# McPiFace-RGBPanel-V2.net
KiCad netlist of a schematic drawn in EAGLE
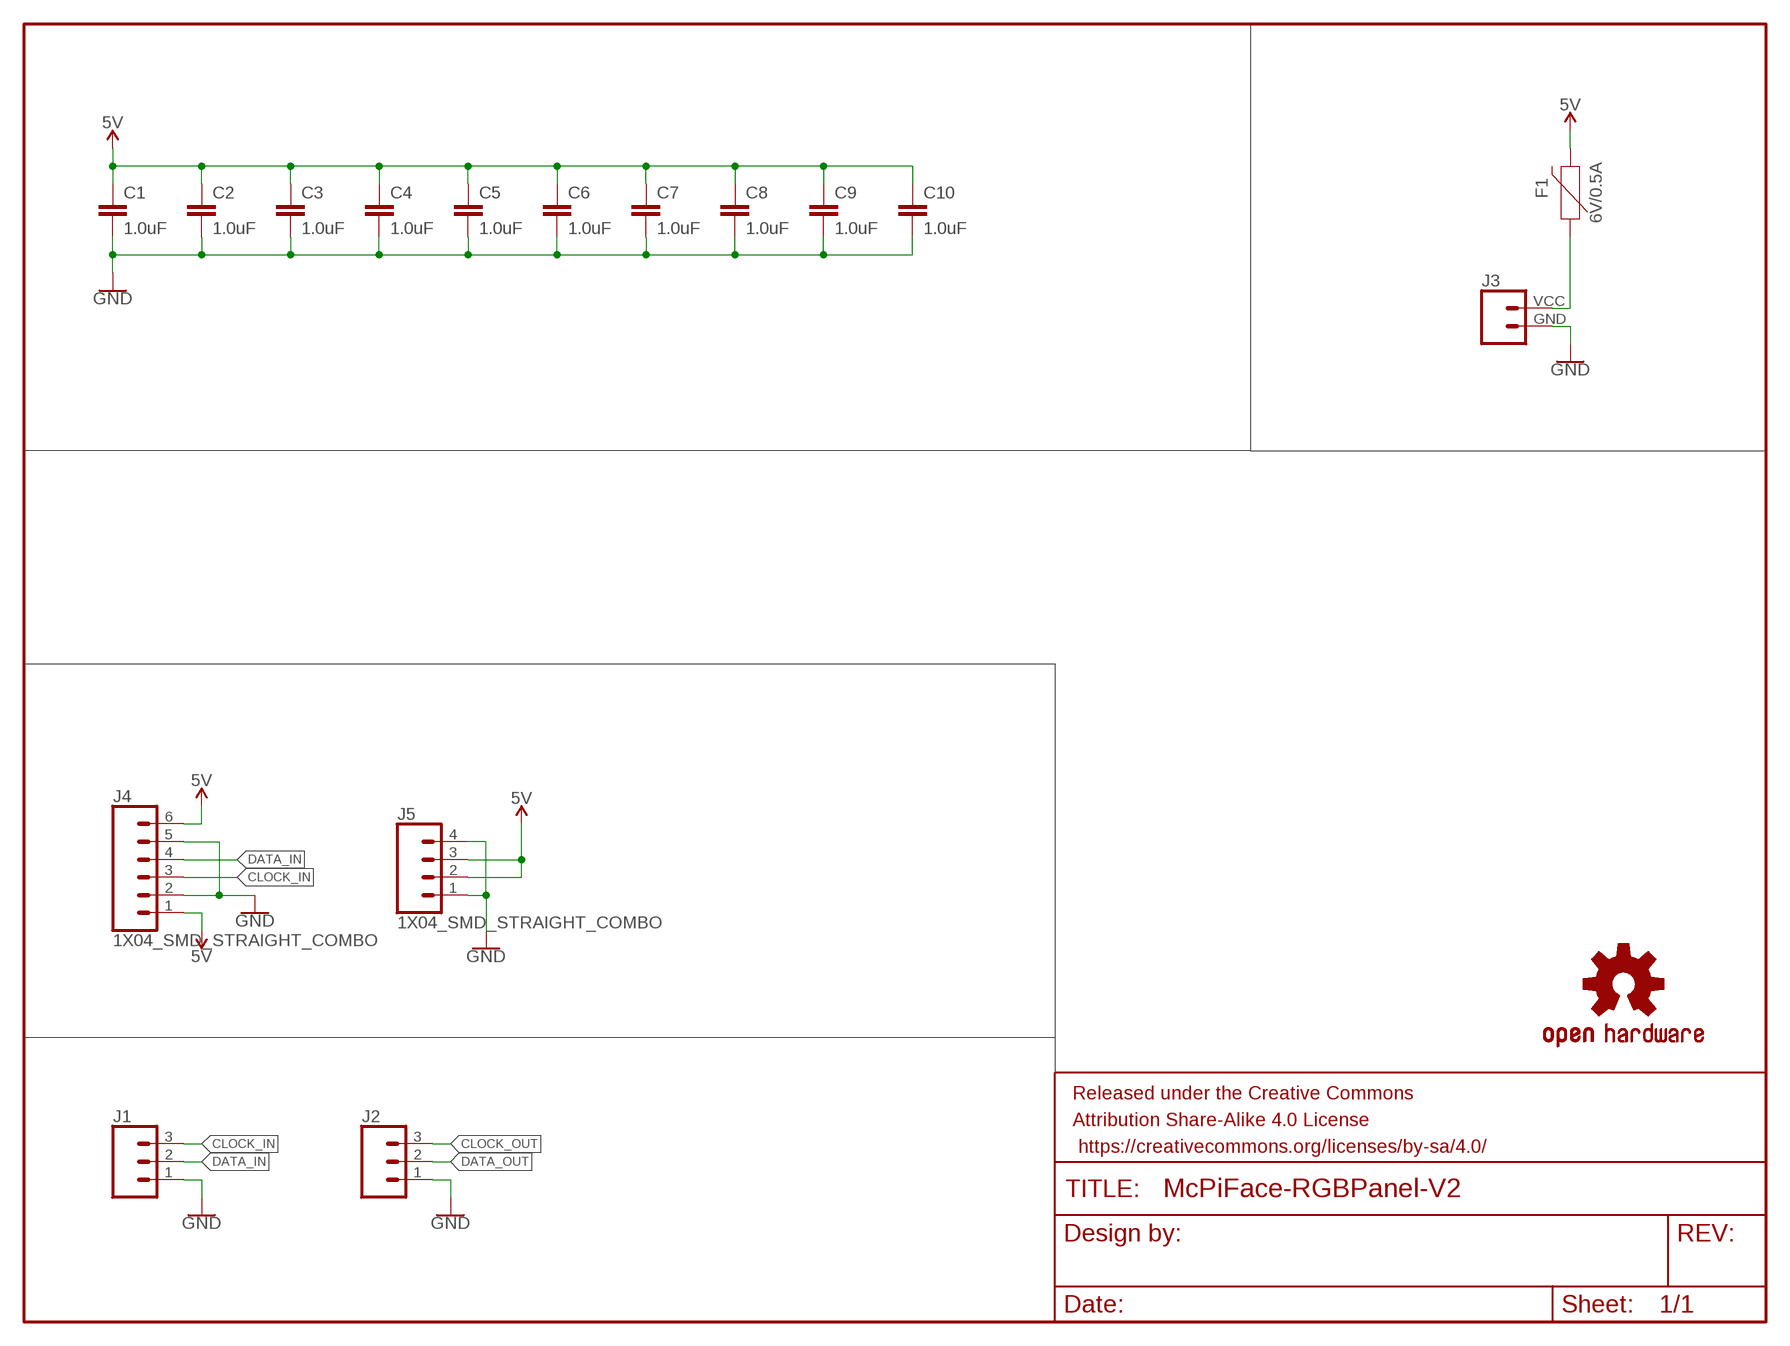
[diagram p0: schematic, sheet 1, part 1 of 2]
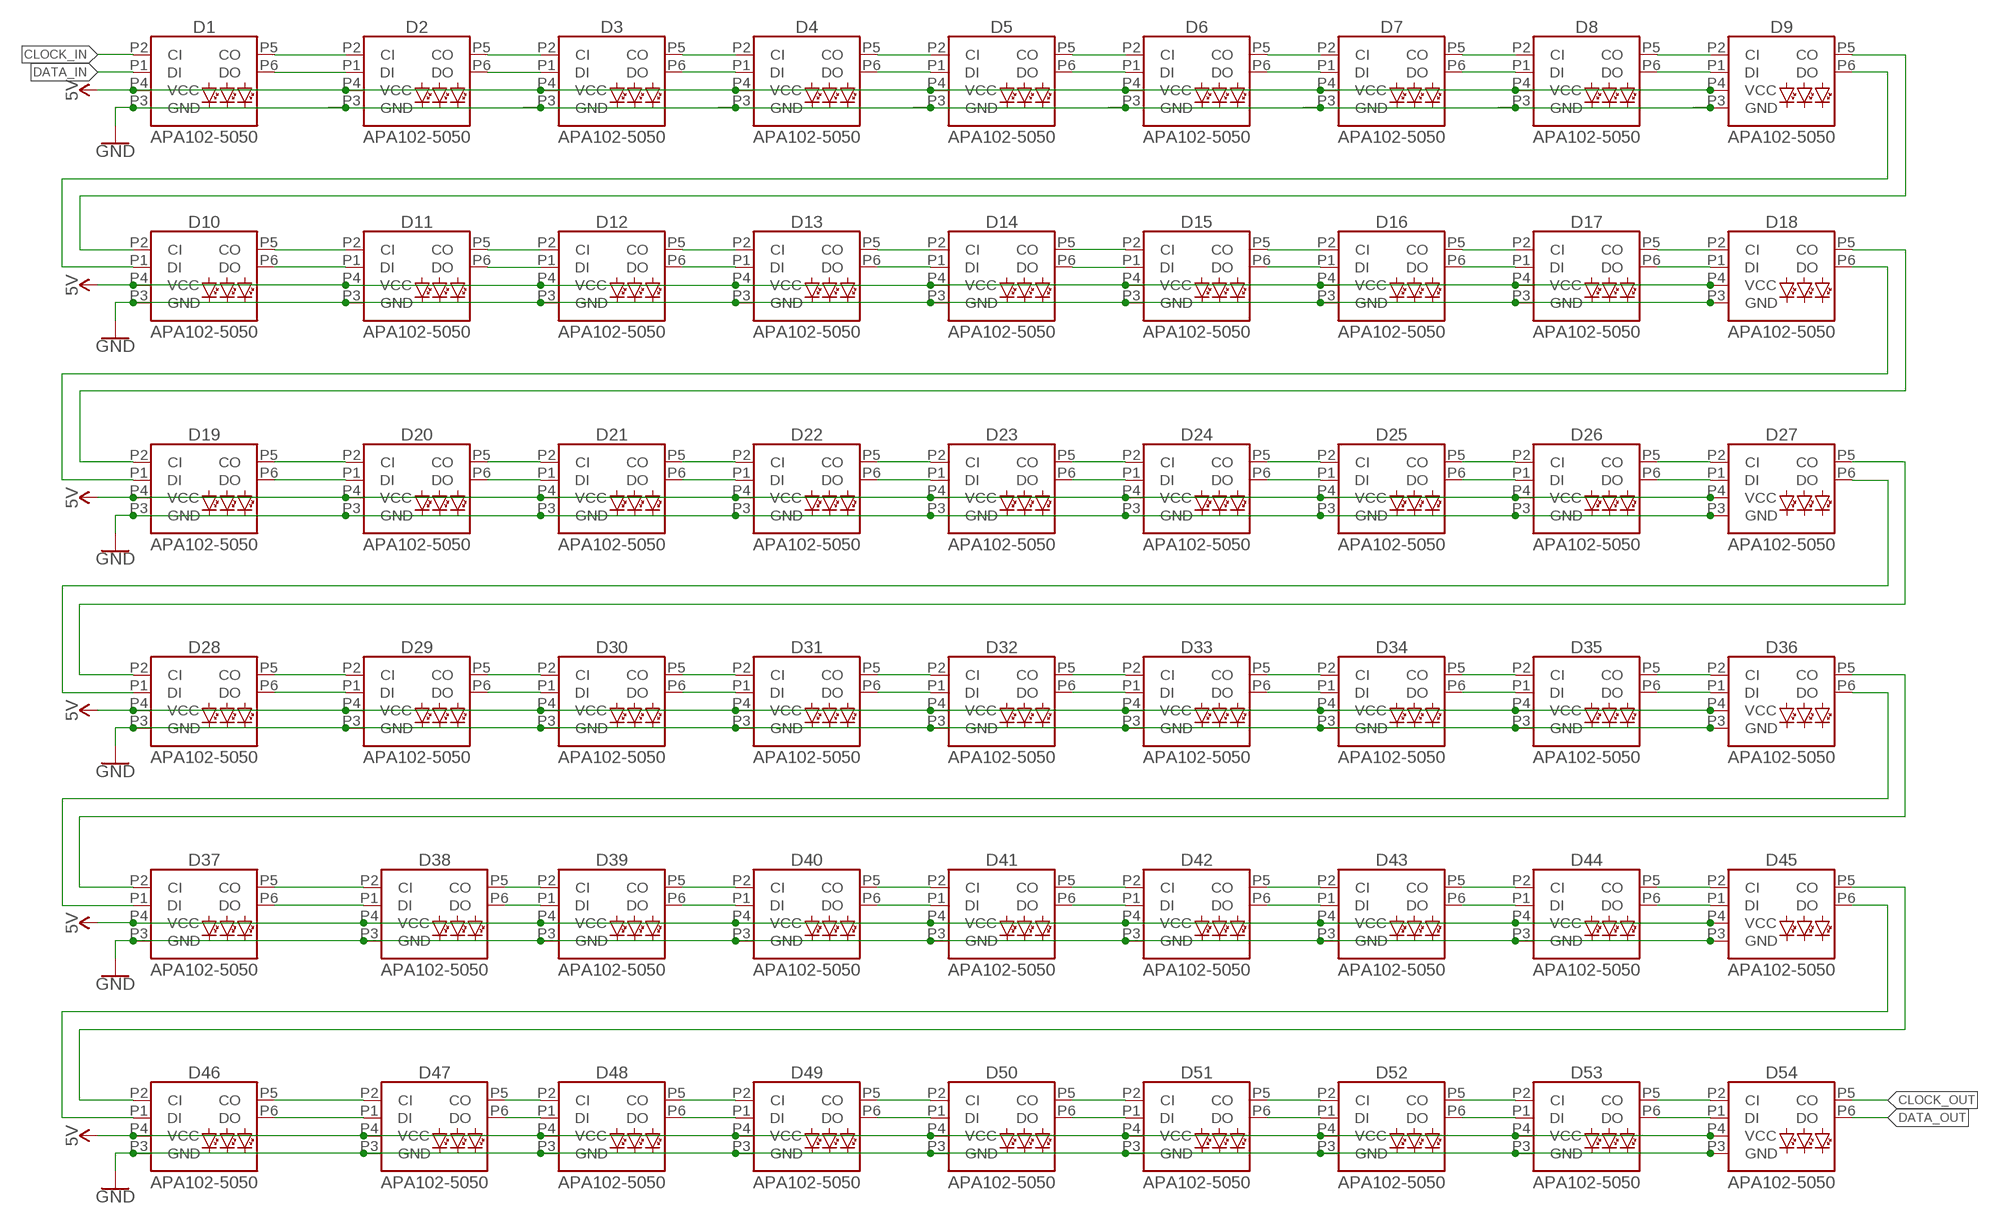
[diagram p1: schematic, sheet 1, part 2 of 2]

(export (version "E")
  (design (tool "Eeschema 10.0.6"))
  (components
    (comp (ref "C1")
      (value "1.0uF")
      (footprint "eagle-import:0805-CAP")
      (libsource (lib "eagle-import") (part "1.0UF-25V-+80/-20(0805){dblquote}"))
    )
    (comp (ref "C2")
      (value "1.0uF")
      (footprint "eagle-import:0805-CAP")
      (libsource (lib "eagle-import") (part "1.0UF-25V-+80/-20(0805){dblquote}"))
    )
    (comp (ref "C3")
      (value "1.0uF")
      (footprint "eagle-import:0805-CAP")
      (libsource (lib "eagle-import") (part "1.0UF-25V-+80/-20(0805){dblquote}"))
    )
    (comp (ref "C4")
      (value "1.0uF")
      (footprint "eagle-import:0805-CAP")
      (libsource (lib "eagle-import") (part "1.0UF-25V-+80/-20(0805){dblquote}"))
    )
    (comp (ref "C5")
      (value "1.0uF")
      (footprint "eagle-import:0805-CAP")
      (libsource (lib "eagle-import") (part "1.0UF-25V-+80/-20(0805){dblquote}"))
    )
    (comp (ref "C6")
      (value "1.0uF")
      (footprint "eagle-import:0805-CAP")
      (libsource (lib "eagle-import") (part "1.0UF-25V-+80/-20(0805){dblquote}"))
    )
    (comp (ref "C7")
      (value "1.0uF")
      (footprint "eagle-import:0805-CAP")
      (libsource (lib "eagle-import") (part "1.0UF-25V-+80/-20(0805){dblquote}"))
    )
    (comp (ref "C8")
      (value "1.0uF")
      (footprint "eagle-import:0805-CAP")
      (libsource (lib "eagle-import") (part "1.0UF-25V-+80/-20(0805){dblquote}"))
    )
    (comp (ref "C9")
      (value "1.0uF")
      (footprint "eagle-import:0805-CAP")
      (libsource (lib "eagle-import") (part "1.0UF-25V-+80/-20(0805){dblquote}"))
    )
    (comp (ref "C10")
      (value "1.0uF")
      (footprint "eagle-import:0805-CAP")
      (libsource (lib "eagle-import") (part "1.0UF-25V-+80/-20(0805){dblquote}"))
    )
    (comp (ref "D1")
      (value "APA102-5050")
      (footprint "eagle-import:APA102-5050")
      (libsource (lib "eagle-import") (part "APA102-5050"))
    )
    (comp (ref "D2")
      (value "APA102-5050")
      (footprint "eagle-import:APA102-5050")
      (libsource (lib "eagle-import") (part "APA102-5050"))
    )
    (comp (ref "D3")
      (value "APA102-5050")
      (footprint "eagle-import:APA102-5050")
      (libsource (lib "eagle-import") (part "APA102-5050"))
    )
    (comp (ref "D4")
      (value "APA102-5050")
      (footprint "eagle-import:APA102-5050")
      (libsource (lib "eagle-import") (part "APA102-5050"))
    )
    (comp (ref "D5")
      (value "APA102-5050")
      (footprint "eagle-import:APA102-5050")
      (libsource (lib "eagle-import") (part "APA102-5050"))
    )
    (comp (ref "D6")
      (value "APA102-5050")
      (footprint "eagle-import:APA102-5050")
      (libsource (lib "eagle-import") (part "APA102-5050"))
    )
    (comp (ref "D7")
      (value "APA102-5050")
      (footprint "eagle-import:APA102-5050")
      (libsource (lib "eagle-import") (part "APA102-5050"))
    )
    (comp (ref "D8")
      (value "APA102-5050")
      (footprint "eagle-import:APA102-5050")
      (libsource (lib "eagle-import") (part "APA102-5050"))
    )
    (comp (ref "D9")
      (value "APA102-5050")
      (footprint "eagle-import:APA102-5050")
      (libsource (lib "eagle-import") (part "APA102-5050"))
    )
    (comp (ref "D10")
      (value "APA102-5050")
      (footprint "eagle-import:APA102-5050")
      (libsource (lib "eagle-import") (part "APA102-5050"))
    )
    (comp (ref "D11")
      (value "APA102-5050")
      (footprint "eagle-import:APA102-5050")
      (libsource (lib "eagle-import") (part "APA102-5050"))
    )
    (comp (ref "D12")
      (value "APA102-5050")
      (footprint "eagle-import:APA102-5050")
      (libsource (lib "eagle-import") (part "APA102-5050"))
    )
    (comp (ref "D13")
      (value "APA102-5050")
      (footprint "eagle-import:APA102-5050")
      (libsource (lib "eagle-import") (part "APA102-5050"))
    )
    (comp (ref "D14")
      (value "APA102-5050")
      (footprint "eagle-import:APA102-5050")
      (libsource (lib "eagle-import") (part "APA102-5050"))
    )
    (comp (ref "D15")
      (value "APA102-5050")
      (footprint "eagle-import:APA102-5050")
      (libsource (lib "eagle-import") (part "APA102-5050"))
    )
    (comp (ref "D16")
      (value "APA102-5050")
      (footprint "eagle-import:APA102-5050")
      (libsource (lib "eagle-import") (part "APA102-5050"))
    )
    (comp (ref "D17")
      (value "APA102-5050")
      (footprint "eagle-import:APA102-5050")
      (libsource (lib "eagle-import") (part "APA102-5050"))
    )
    (comp (ref "D18")
      (value "APA102-5050")
      (footprint "eagle-import:APA102-5050")
      (libsource (lib "eagle-import") (part "APA102-5050"))
    )
    (comp (ref "D19")
      (value "APA102-5050")
      (footprint "eagle-import:APA102-5050")
      (libsource (lib "eagle-import") (part "APA102-5050"))
    )
    (comp (ref "D20")
      (value "APA102-5050")
      (footprint "eagle-import:APA102-5050")
      (libsource (lib "eagle-import") (part "APA102-5050"))
    )
    (comp (ref "D21")
      (value "APA102-5050")
      (footprint "eagle-import:APA102-5050")
      (libsource (lib "eagle-import") (part "APA102-5050"))
    )
    (comp (ref "D22")
      (value "APA102-5050")
      (footprint "eagle-import:APA102-5050")
      (libsource (lib "eagle-import") (part "APA102-5050"))
    )
    (comp (ref "D23")
      (value "APA102-5050")
      (footprint "eagle-import:APA102-5050")
      (libsource (lib "eagle-import") (part "APA102-5050"))
    )
    (comp (ref "D24")
      (value "APA102-5050")
      (footprint "eagle-import:APA102-5050")
      (libsource (lib "eagle-import") (part "APA102-5050"))
    )
    (comp (ref "D25")
      (value "APA102-5050")
      (footprint "eagle-import:APA102-5050")
      (libsource (lib "eagle-import") (part "APA102-5050"))
    )
    (comp (ref "D26")
      (value "APA102-5050")
      (footprint "eagle-import:APA102-5050")
      (libsource (lib "eagle-import") (part "APA102-5050"))
    )
    (comp (ref "D27")
      (value "APA102-5050")
      (footprint "eagle-import:APA102-5050")
      (libsource (lib "eagle-import") (part "APA102-5050"))
    )
    (comp (ref "D28")
      (value "APA102-5050")
      (footprint "eagle-import:APA102-5050")
      (libsource (lib "eagle-import") (part "APA102-5050"))
    )
    (comp (ref "D29")
      (value "APA102-5050")
      (footprint "eagle-import:APA102-5050")
      (libsource (lib "eagle-import") (part "APA102-5050"))
    )
    (comp (ref "D30")
      (value "APA102-5050")
      (footprint "eagle-import:APA102-5050")
      (libsource (lib "eagle-import") (part "APA102-5050"))
    )
    (comp (ref "D31")
      (value "APA102-5050")
      (footprint "eagle-import:APA102-5050")
      (libsource (lib "eagle-import") (part "APA102-5050"))
    )
    (comp (ref "D32")
      (value "APA102-5050")
      (footprint "eagle-import:APA102-5050")
      (libsource (lib "eagle-import") (part "APA102-5050"))
    )
    (comp (ref "D33")
      (value "APA102-5050")
      (footprint "eagle-import:APA102-5050")
      (libsource (lib "eagle-import") (part "APA102-5050"))
    )
    (comp (ref "D34")
      (value "APA102-5050")
      (footprint "eagle-import:APA102-5050")
      (libsource (lib "eagle-import") (part "APA102-5050"))
    )
    (comp (ref "D35")
      (value "APA102-5050")
      (footprint "eagle-import:APA102-5050")
      (libsource (lib "eagle-import") (part "APA102-5050"))
    )
    (comp (ref "D36")
      (value "APA102-5050")
      (footprint "eagle-import:APA102-5050")
      (libsource (lib "eagle-import") (part "APA102-5050"))
    )
    (comp (ref "D37")
      (value "APA102-5050")
      (footprint "eagle-import:APA102-5050")
      (libsource (lib "eagle-import") (part "APA102-5050"))
    )
    (comp (ref "D38")
      (value "APA102-5050")
      (footprint "eagle-import:APA102-5050")
      (libsource (lib "eagle-import") (part "APA102-5050"))
    )
    (comp (ref "D39")
      (value "APA102-5050")
      (footprint "eagle-import:APA102-5050")
      (libsource (lib "eagle-import") (part "APA102-5050"))
    )
    (comp (ref "D40")
      (value "APA102-5050")
      (footprint "eagle-import:APA102-5050")
      (libsource (lib "eagle-import") (part "APA102-5050"))
    )
    (comp (ref "D41")
      (value "APA102-5050")
      (footprint "eagle-import:APA102-5050")
      (libsource (lib "eagle-import") (part "APA102-5050"))
    )
    (comp (ref "D42")
      (value "APA102-5050")
      (footprint "eagle-import:APA102-5050")
      (libsource (lib "eagle-import") (part "APA102-5050"))
    )
    (comp (ref "D43")
      (value "APA102-5050")
      (footprint "eagle-import:APA102-5050")
      (libsource (lib "eagle-import") (part "APA102-5050"))
    )
    (comp (ref "D44")
      (value "APA102-5050")
      (footprint "eagle-import:APA102-5050")
      (libsource (lib "eagle-import") (part "APA102-5050"))
    )
    (comp (ref "D45")
      (value "APA102-5050")
      (footprint "eagle-import:APA102-5050")
      (libsource (lib "eagle-import") (part "APA102-5050"))
    )
    (comp (ref "D46")
      (value "APA102-5050")
      (footprint "eagle-import:APA102-5050")
      (libsource (lib "eagle-import") (part "APA102-5050"))
    )
    (comp (ref "D47")
      (value "APA102-5050")
      (footprint "eagle-import:APA102-5050")
      (libsource (lib "eagle-import") (part "APA102-5050"))
    )
    (comp (ref "D48")
      (value "APA102-5050")
      (footprint "eagle-import:APA102-5050")
      (libsource (lib "eagle-import") (part "APA102-5050"))
    )
    (comp (ref "D49")
      (value "APA102-5050")
      (footprint "eagle-import:APA102-5050")
      (libsource (lib "eagle-import") (part "APA102-5050"))
    )
    (comp (ref "D50")
      (value "APA102-5050")
      (footprint "eagle-import:APA102-5050")
      (libsource (lib "eagle-import") (part "APA102-5050"))
    )
    (comp (ref "D51")
      (value "APA102-5050")
      (footprint "eagle-import:APA102-5050")
      (libsource (lib "eagle-import") (part "APA102-5050"))
    )
    (comp (ref "D52")
      (value "APA102-5050")
      (footprint "eagle-import:APA102-5050")
      (libsource (lib "eagle-import") (part "APA102-5050"))
    )
    (comp (ref "D53")
      (value "APA102-5050")
      (footprint "eagle-import:APA102-5050")
      (libsource (lib "eagle-import") (part "APA102-5050"))
    )
    (comp (ref "D54")
      (value "APA102-5050")
      (footprint "eagle-import:APA102-5050")
      (libsource (lib "eagle-import") (part "APA102-5050"))
    )
    (comp (ref "F1")
      (value "6V/0.5A")
      (footprint "eagle-import:1206")
      (libsource (lib "eagle-import") (part "PPTC_HALF-AMP"))
    )
    (comp (ref "FRAME1")
      (value "FRAME-LETTER")
      (footprint "eagle-import:CREATIVE_COMMONS")
      (libsource (lib "eagle-import") (part "FRAME-LETTER"))
    )
    (comp (ref "J1")
      (value "CONN_03SMD")
      (footprint "eagle-import:1X03-1MM-RA")
      (libsource (lib "eagle-import") (part "CONN_03SMD"))
    )
    (comp (ref "J2")
      (value "CONN_03SMD")
      (footprint "eagle-import:1X03-1MM-RA")
      (libsource (lib "eagle-import") (part "CONN_03SMD"))
    )
    (comp (ref "J3")
      (value "CONN_02JST-2-PH-VERT")
      (footprint "eagle-import:JST-2-SMD-VERT")
      (libsource (lib "eagle-import") (part "CONN_02JST-2-PH-VERT"))
    )
    (comp (ref "J4")
      (value "1X04_SMD_STRAIGHT_COMBO")
      (footprint "eagle-import:1X06_SMD_STRAIGHT_COMBO")
      (libsource (lib "eagle-import") (part "CONN_06SMD-STRAIGHT-COMBO-FEMALE"))
    )
    (comp (ref "J5")
      (value "1X04_SMD_STRAIGHT_COMBO")
      (footprint "eagle-import:1X04_SMD_VERTICAL_COMBO")
      (libsource (lib "eagle-import") (part "CONN_04SMD_STRAIGHT_COMBO"))
    )
    (comp (ref "LOGO1")
      (value "OSHW-LOGOL")
      (footprint "eagle-import:OSHW-LOGO-L")
      (libsource (lib "eagle-import") (part "OSHW-LOGOL"))
    )
  )
  (nets
    (net (code "1") (name "5V") (class "Default")
      (node (ref "C1") (pin "1") (pinfunction "1_1") (pintype "passive"))
      (node (ref "C10") (pin "1") (pinfunction "1_1") (pintype "passive"))
      (node (ref "C2") (pin "1") (pinfunction "1_1") (pintype "passive"))
      (node (ref "C3") (pin "1") (pinfunction "1_1") (pintype "passive"))
      (node (ref "C4") (pin "1") (pinfunction "1_1") (pintype "passive"))
      (node (ref "C5") (pin "1") (pinfunction "1_1") (pintype "passive"))
      (node (ref "C6") (pin "1") (pinfunction "1_1") (pintype "passive"))
      (node (ref "C7") (pin "1") (pinfunction "1_1") (pintype "passive"))
      (node (ref "C8") (pin "1") (pinfunction "1_1") (pintype "passive"))
      (node (ref "C9") (pin "1") (pinfunction "1_1") (pintype "passive"))
      (node (ref "D1") (pin "P4") (pinfunction "VCC_P4") (pintype "bidirectional"))
      (node (ref "D10") (pin "P4") (pinfunction "VCC_P4") (pintype "bidirectional"))
      (node (ref "D11") (pin "P4") (pinfunction "VCC_P4") (pintype "bidirectional"))
      (node (ref "D12") (pin "P4") (pinfunction "VCC_P4") (pintype "bidirectional"))
      (node (ref "D13") (pin "P4") (pinfunction "VCC_P4") (pintype "bidirectional"))
      (node (ref "D14") (pin "P4") (pinfunction "VCC_P4") (pintype "bidirectional"))
      (node (ref "D15") (pin "P4") (pinfunction "VCC_P4") (pintype "bidirectional"))
      (node (ref "D16") (pin "P4") (pinfunction "VCC_P4") (pintype "bidirectional"))
      (node (ref "D17") (pin "P4") (pinfunction "VCC_P4") (pintype "bidirectional"))
      (node (ref "D18") (pin "P4") (pinfunction "VCC_P4") (pintype "bidirectional"))
      (node (ref "D19") (pin "P4") (pinfunction "VCC_P4") (pintype "bidirectional"))
      (node (ref "D2") (pin "P4") (pinfunction "VCC_P4") (pintype "bidirectional"))
      (node (ref "D20") (pin "P4") (pinfunction "VCC_P4") (pintype "bidirectional"))
      (node (ref "D21") (pin "P4") (pinfunction "VCC_P4") (pintype "bidirectional"))
      (node (ref "D22") (pin "P4") (pinfunction "VCC_P4") (pintype "bidirectional"))
      (node (ref "D23") (pin "P4") (pinfunction "VCC_P4") (pintype "bidirectional"))
      (node (ref "D24") (pin "P4") (pinfunction "VCC_P4") (pintype "bidirectional"))
      (node (ref "D25") (pin "P4") (pinfunction "VCC_P4") (pintype "bidirectional"))
      (node (ref "D26") (pin "P4") (pinfunction "VCC_P4") (pintype "bidirectional"))
      (node (ref "D27") (pin "P4") (pinfunction "VCC_P4") (pintype "bidirectional"))
      (node (ref "D28") (pin "P4") (pinfunction "VCC_P4") (pintype "bidirectional"))
      (node (ref "D29") (pin "P4") (pinfunction "VCC_P4") (pintype "bidirectional"))
      (node (ref "D3") (pin "P4") (pinfunction "VCC_P4") (pintype "bidirectional"))
      (node (ref "D30") (pin "P4") (pinfunction "VCC_P4") (pintype "bidirectional"))
      (node (ref "D31") (pin "P4") (pinfunction "VCC_P4") (pintype "bidirectional"))
      (node (ref "D32") (pin "P4") (pinfunction "VCC_P4") (pintype "bidirectional"))
      (node (ref "D33") (pin "P4") (pinfunction "VCC_P4") (pintype "bidirectional"))
      (node (ref "D34") (pin "P4") (pinfunction "VCC_P4") (pintype "bidirectional"))
      (node (ref "D35") (pin "P4") (pinfunction "VCC_P4") (pintype "bidirectional"))
      (node (ref "D36") (pin "P4") (pinfunction "VCC_P4") (pintype "bidirectional"))
      (node (ref "D37") (pin "P4") (pinfunction "VCC_P4") (pintype "bidirectional"))
      (node (ref "D38") (pin "P4") (pinfunction "VCC_P4") (pintype "bidirectional"))
      (node (ref "D39") (pin "P4") (pinfunction "VCC_P4") (pintype "bidirectional"))
      (node (ref "D4") (pin "P4") (pinfunction "VCC_P4") (pintype "bidirectional"))
      (node (ref "D40") (pin "P4") (pinfunction "VCC_P4") (pintype "bidirectional"))
      (node (ref "D41") (pin "P4") (pinfunction "VCC_P4") (pintype "bidirectional"))
      (node (ref "D42") (pin "P4") (pinfunction "VCC_P4") (pintype "bidirectional"))
      (node (ref "D43") (pin "P4") (pinfunction "VCC_P4") (pintype "bidirectional"))
      (node (ref "D44") (pin "P4") (pinfunction "VCC_P4") (pintype "bidirectional"))
      (node (ref "D45") (pin "P4") (pinfunction "VCC_P4") (pintype "bidirectional"))
      (node (ref "D46") (pin "P4") (pinfunction "VCC_P4") (pintype "bidirectional"))
      (node (ref "D47") (pin "P4") (pinfunction "VCC_P4") (pintype "bidirectional"))
      (node (ref "D48") (pin "P4") (pinfunction "VCC_P4") (pintype "bidirectional"))
      (node (ref "D49") (pin "P4") (pinfunction "VCC_P4") (pintype "bidirectional"))
      (node (ref "D5") (pin "P4") (pinfunction "VCC_P4") (pintype "bidirectional"))
      (node (ref "D50") (pin "P4") (pinfunction "VCC_P4") (pintype "bidirectional"))
      (node (ref "D51") (pin "P4") (pinfunction "VCC_P4") (pintype "bidirectional"))
      (node (ref "D52") (pin "P4") (pinfunction "VCC_P4") (pintype "bidirectional"))
      (node (ref "D53") (pin "P4") (pinfunction "VCC_P4") (pintype "bidirectional"))
      (node (ref "D54") (pin "P4") (pinfunction "VCC_P4") (pintype "bidirectional"))
      (node (ref "D6") (pin "P4") (pinfunction "VCC_P4") (pintype "bidirectional"))
      (node (ref "D7") (pin "P4") (pinfunction "VCC_P4") (pintype "bidirectional"))
      (node (ref "D8") (pin "P4") (pinfunction "VCC_P4") (pintype "bidirectional"))
      (node (ref "D9") (pin "P4") (pinfunction "VCC_P4") (pintype "bidirectional"))
      (node (ref "F1") (pin "2") (pinfunction "2_2") (pintype "bidirectional"))
      (node (ref "J4") (pin "1") (pinfunction "1_1") (pintype "passive"))
      (node (ref "J4") (pin "6") (pinfunction "6_6") (pintype "passive"))
      (node (ref "J5") (pin "2") (pinfunction "2_2") (pintype "passive"))
      (node (ref "J5") (pin "3") (pinfunction "3_3") (pintype "passive"))
    )
    (net (code "2") (name "CLOCK_IN") (class "Default")
      (node (ref "D1") (pin "P2") (pinfunction "CI_P2") (pintype "bidirectional"))
      (node (ref "J1") (pin "3") (pinfunction "3_3") (pintype "passive"))
      (node (ref "J4") (pin "3") (pinfunction "3_3") (pintype "passive"))
    )
    (net (code "3") (name "CLOCK_OUT") (class "Default")
      (node (ref "D54") (pin "P5") (pinfunction "CO_P5") (pintype "bidirectional"))
      (node (ref "J2") (pin "3") (pinfunction "3_3") (pintype "passive"))
    )
    (net (code "4") (name "DATA_IN") (class "Default")
      (node (ref "D1") (pin "P1") (pinfunction "DI_P1") (pintype "bidirectional"))
      (node (ref "J1") (pin "2") (pinfunction "2_2") (pintype "passive"))
      (node (ref "J4") (pin "4") (pinfunction "4_4") (pintype "passive"))
    )
    (net (code "5") (name "DATA_OUT") (class "Default")
      (node (ref "D54") (pin "P6") (pinfunction "DO_P6") (pintype "bidirectional"))
      (node (ref "J2") (pin "2") (pinfunction "2_2") (pintype "passive"))
    )
    (net (code "6") (name "GND") (class "Default")
      (node (ref "C1") (pin "2") (pinfunction "2_2") (pintype "passive"))
      (node (ref "C10") (pin "2") (pinfunction "2_2") (pintype "passive"))
      (node (ref "C2") (pin "2") (pinfunction "2_2") (pintype "passive"))
      (node (ref "C3") (pin "2") (pinfunction "2_2") (pintype "passive"))
      (node (ref "C4") (pin "2") (pinfunction "2_2") (pintype "passive"))
      (node (ref "C5") (pin "2") (pinfunction "2_2") (pintype "passive"))
      (node (ref "C6") (pin "2") (pinfunction "2_2") (pintype "passive"))
      (node (ref "C7") (pin "2") (pinfunction "2_2") (pintype "passive"))
      (node (ref "C8") (pin "2") (pinfunction "2_2") (pintype "passive"))
      (node (ref "C9") (pin "2") (pinfunction "2_2") (pintype "passive"))
      (node (ref "D1") (pin "P3") (pinfunction "GND_P3") (pintype "bidirectional"))
      (node (ref "D10") (pin "P3") (pinfunction "GND_P3") (pintype "bidirectional"))
      (node (ref "D11") (pin "P3") (pinfunction "GND_P3") (pintype "bidirectional"))
      (node (ref "D12") (pin "P3") (pinfunction "GND_P3") (pintype "bidirectional"))
      (node (ref "D13") (pin "P3") (pinfunction "GND_P3") (pintype "bidirectional"))
      (node (ref "D14") (pin "P3") (pinfunction "GND_P3") (pintype "bidirectional"))
      (node (ref "D15") (pin "P3") (pinfunction "GND_P3") (pintype "bidirectional"))
      (node (ref "D16") (pin "P3") (pinfunction "GND_P3") (pintype "bidirectional"))
      (node (ref "D17") (pin "P3") (pinfunction "GND_P3") (pintype "bidirectional"))
      (node (ref "D18") (pin "P3") (pinfunction "GND_P3") (pintype "bidirectional"))
      (node (ref "D19") (pin "P3") (pinfunction "GND_P3") (pintype "bidirectional"))
      (node (ref "D2") (pin "P3") (pinfunction "GND_P3") (pintype "bidirectional"))
      (node (ref "D20") (pin "P3") (pinfunction "GND_P3") (pintype "bidirectional"))
      (node (ref "D21") (pin "P3") (pinfunction "GND_P3") (pintype "bidirectional"))
      (node (ref "D22") (pin "P3") (pinfunction "GND_P3") (pintype "bidirectional"))
      (node (ref "D23") (pin "P3") (pinfunction "GND_P3") (pintype "bidirectional"))
      (node (ref "D24") (pin "P3") (pinfunction "GND_P3") (pintype "bidirectional"))
      (node (ref "D25") (pin "P3") (pinfunction "GND_P3") (pintype "bidirectional"))
      (node (ref "D26") (pin "P3") (pinfunction "GND_P3") (pintype "bidirectional"))
      (node (ref "D27") (pin "P3") (pinfunction "GND_P3") (pintype "bidirectional"))
      (node (ref "D28") (pin "P3") (pinfunction "GND_P3") (pintype "bidirectional"))
      (node (ref "D29") (pin "P3") (pinfunction "GND_P3") (pintype "bidirectional"))
      (node (ref "D3") (pin "P3") (pinfunction "GND_P3") (pintype "bidirectional"))
      (node (ref "D30") (pin "P3") (pinfunction "GND_P3") (pintype "bidirectional"))
      (node (ref "D31") (pin "P3") (pinfunction "GND_P3") (pintype "bidirectional"))
      (node (ref "D32") (pin "P3") (pinfunction "GND_P3") (pintype "bidirectional"))
      (node (ref "D33") (pin "P3") (pinfunction "GND_P3") (pintype "bidirectional"))
      (node (ref "D34") (pin "P3") (pinfunction "GND_P3") (pintype "bidirectional"))
      (node (ref "D35") (pin "P3") (pinfunction "GND_P3") (pintype "bidirectional"))
      (node (ref "D36") (pin "P3") (pinfunction "GND_P3") (pintype "bidirectional"))
      (node (ref "D37") (pin "P3") (pinfunction "GND_P3") (pintype "bidirectional"))
      (node (ref "D38") (pin "P3") (pinfunction "GND_P3") (pintype "bidirectional"))
      (node (ref "D39") (pin "P3") (pinfunction "GND_P3") (pintype "bidirectional"))
      (node (ref "D4") (pin "P3") (pinfunction "GND_P3") (pintype "bidirectional"))
      (node (ref "D40") (pin "P3") (pinfunction "GND_P3") (pintype "bidirectional"))
      (node (ref "D41") (pin "P3") (pinfunction "GND_P3") (pintype "bidirectional"))
      (node (ref "D42") (pin "P3") (pinfunction "GND_P3") (pintype "bidirectional"))
      (node (ref "D43") (pin "P3") (pinfunction "GND_P3") (pintype "bidirectional"))
      (node (ref "D44") (pin "P3") (pinfunction "GND_P3") (pintype "bidirectional"))
      (node (ref "D45") (pin "P3") (pinfunction "GND_P3") (pintype "bidirectional"))
      (node (ref "D46") (pin "P3") (pinfunction "GND_P3") (pintype "bidirectional"))
      (node (ref "D47") (pin "P3") (pinfunction "GND_P3") (pintype "bidirectional"))
      (node (ref "D48") (pin "P3") (pinfunction "GND_P3") (pintype "bidirectional"))
      (node (ref "D49") (pin "P3") (pinfunction "GND_P3") (pintype "bidirectional"))
      (node (ref "D5") (pin "P3") (pinfunction "GND_P3") (pintype "bidirectional"))
      (node (ref "D50") (pin "P3") (pinfunction "GND_P3") (pintype "bidirectional"))
      (node (ref "D51") (pin "P3") (pinfunction "GND_P3") (pintype "bidirectional"))
      (node (ref "D52") (pin "P3") (pinfunction "GND_P3") (pintype "bidirectional"))
      (node (ref "D53") (pin "P3") (pinfunction "GND_P3") (pintype "bidirectional"))
      (node (ref "D54") (pin "P3") (pinfunction "GND_P3") (pintype "bidirectional"))
      (node (ref "D6") (pin "P3") (pinfunction "GND_P3") (pintype "bidirectional"))
      (node (ref "D7") (pin "P3") (pinfunction "GND_P3") (pintype "bidirectional"))
      (node (ref "D8") (pin "P3") (pinfunction "GND_P3") (pintype "bidirectional"))
      (node (ref "D9") (pin "P3") (pinfunction "GND_P3") (pintype "bidirectional"))
      (node (ref "J1") (pin "1") (pinfunction "1_1") (pintype "passive"))
      (node (ref "J2") (pin "1") (pinfunction "1_1") (pintype "passive"))
      (node (ref "J3") (pin "GND") (pinfunction "1_GND") (pintype "passive"))
      (node (ref "J4") (pin "2") (pinfunction "2_2") (pintype "passive"))
      (node (ref "J4") (pin "5") (pinfunction "5_5") (pintype "passive"))
      (node (ref "J5") (pin "1") (pinfunction "1_1") (pintype "passive"))
      (node (ref "J5") (pin "4") (pinfunction "4_4") (pintype "passive"))
    )
    (net (code "7") (name "Net-(D1-CO)") (class "Default")
      (node (ref "D1") (pin "P5") (pinfunction "CO_P5") (pintype "bidirectional"))
      (node (ref "D2") (pin "P2") (pinfunction "CI_P2") (pintype "bidirectional"))
    )
    (net (code "8") (name "Net-(D1-DO)") (class "Default")
      (node (ref "D1") (pin "P6") (pinfunction "DO_P6") (pintype "bidirectional"))
      (node (ref "D2") (pin "P1") (pinfunction "DI_P1") (pintype "bidirectional"))
    )
    (net (code "9") (name "Net-(D2-CO)") (class "Default")
      (node (ref "D2") (pin "P5") (pinfunction "CO_P5") (pintype "bidirectional"))
      (node (ref "D3") (pin "P2") (pinfunction "CI_P2") (pintype "bidirectional"))
    )
    (net (code "10") (name "Net-(D2-DO)") (class "Default")
      (node (ref "D2") (pin "P6") (pinfunction "DO_P6") (pintype "bidirectional"))
      (node (ref "D3") (pin "P1") (pinfunction "DI_P1") (pintype "bidirectional"))
    )
    (net (code "11") (name "Net-(D3-CO)") (class "Default")
      (node (ref "D3") (pin "P5") (pinfunction "CO_P5") (pintype "bidirectional"))
      (node (ref "D4") (pin "P2") (pinfunction "CI_P2") (pintype "bidirectional"))
    )
    (net (code "12") (name "Net-(D3-DO)") (class "Default")
      (node (ref "D3") (pin "P6") (pinfunction "DO_P6") (pintype "bidirectional"))
      (node (ref "D4") (pin "P1") (pinfunction "DI_P1") (pintype "bidirectional"))
    )
    (net (code "13") (name "Net-(D4-CO)") (class "Default")
      (node (ref "D4") (pin "P5") (pinfunction "CO_P5") (pintype "bidirectional"))
      (node (ref "D5") (pin "P2") (pinfunction "CI_P2") (pintype "bidirectional"))
    )
    (net (code "14") (name "Net-(D4-DO)") (class "Default")
      (node (ref "D4") (pin "P6") (pinfunction "DO_P6") (pintype "bidirectional"))
      (node (ref "D5") (pin "P1") (pinfunction "DI_P1") (pintype "bidirectional"))
    )
    (net (code "15") (name "Net-(D5-CO)") (class "Default")
      (node (ref "D5") (pin "P5") (pinfunction "CO_P5") (pintype "bidirectional"))
      (node (ref "D6") (pin "P2") (pinfunction "CI_P2") (pintype "bidirectional"))
    )
    (net (code "16") (name "Net-(D5-DO)") (class "Default")
      (node (ref "D5") (pin "P6") (pinfunction "DO_P6") (pintype "bidirectional"))
      (node (ref "D6") (pin "P1") (pinfunction "DI_P1") (pintype "bidirectional"))
    )
    (net (code "17") (name "Net-(D6-CO)") (class "Default")
      (node (ref "D6") (pin "P5") (pinfunction "CO_P5") (pintype "bidirectional"))
      (node (ref "D7") (pin "P2") (pinfunction "CI_P2") (pintype "bidirectional"))
    )
    (net (code "18") (name "Net-(D6-DO)") (class "Default")
      (node (ref "D6") (pin "P6") (pinfunction "DO_P6") (pintype "bidirectional"))
      (node (ref "D7") (pin "P1") (pinfunction "DI_P1") (pintype "bidirectional"))
    )
    (net (code "19") (name "Net-(D7-CO)") (class "Default")
      (node (ref "D7") (pin "P5") (pinfunction "CO_P5") (pintype "bidirectional"))
      (node (ref "D8") (pin "P2") (pinfunction "CI_P2") (pintype "bidirectional"))
    )
    (net (code "20") (name "Net-(D7-DO)") (class "Default")
      (node (ref "D7") (pin "P6") (pinfunction "DO_P6") (pintype "bidirectional"))
      (node (ref "D8") (pin "P1") (pinfunction "DI_P1") (pintype "bidirectional"))
    )
    (net (code "21") (name "Net-(D8-CO)") (class "Default")
      (node (ref "D8") (pin "P5") (pinfunction "CO_P5") (pintype "bidirectional"))
      (node (ref "D9") (pin "P2") (pinfunction "CI_P2") (pintype "bidirectional"))
    )
    (net (code "22") (name "Net-(D8-DO)") (class "Default")
      (node (ref "D8") (pin "P6") (pinfunction "DO_P6") (pintype "bidirectional"))
      (node (ref "D9") (pin "P1") (pinfunction "DI_P1") (pintype "bidirectional"))
    )
    (net (code "23") (name "Net-(D10-CI)") (class "Default")
      (node (ref "D10") (pin "P2") (pinfunction "CI_P2") (pintype "bidirectional"))
      (node (ref "D9") (pin "P5") (pinfunction "CO_P5") (pintype "bidirectional"))
    )
    (net (code "24") (name "Net-(D10-CO)") (class "Default")
      (node (ref "D10") (pin "P5") (pinfunction "CO_P5") (pintype "bidirectional"))
      (node (ref "D11") (pin "P2") (pinfunction "CI_P2") (pintype "bidirectional"))
    )
    (net (code "25") (name "Net-(D10-DI)") (class "Default")
      (node (ref "D10") (pin "P1") (pinfunction "DI_P1") (pintype "bidirectional"))
      (node (ref "D9") (pin "P6") (pinfunction "DO_P6") (pintype "bidirectional"))
    )
    (net (code "26") (name "Net-(D10-DO)") (class "Default")
      (node (ref "D10") (pin "P6") (pinfunction "DO_P6") (pintype "bidirectional"))
      (node (ref "D11") (pin "P1") (pinfunction "DI_P1") (pintype "bidirectional"))
    )
    (net (code "27") (name "Net-(D11-CO)") (class "Default")
      (node (ref "D11") (pin "P5") (pinfunction "CO_P5") (pintype "bidirectional"))
      (node (ref "D12") (pin "P2") (pinfunction "CI_P2") (pintype "bidirectional"))
    )
    (net (code "28") (name "Net-(D11-DO)") (class "Default")
      (node (ref "D11") (pin "P6") (pinfunction "DO_P6") (pintype "bidirectional"))
      (node (ref "D12") (pin "P1") (pinfunction "DI_P1") (pintype "bidirectional"))
    )
    (net (code "29") (name "Net-(D12-CO)") (class "Default")
      (node (ref "D12") (pin "P5") (pinfunction "CO_P5") (pintype "bidirectional"))
      (node (ref "D13") (pin "P2") (pinfunction "CI_P2") (pintype "bidirectional"))
    )
    (net (code "30") (name "Net-(D12-DO)") (class "Default")
      (node (ref "D12") (pin "P6") (pinfunction "DO_P6") (pintype "bidirectional"))
      (node (ref "D13") (pin "P1") (pinfunction "DI_P1") (pintype "bidirectional"))
    )
    (net (code "31") (name "Net-(D13-CO)") (class "Default")
      (node (ref "D13") (pin "P5") (pinfunction "CO_P5") (pintype "bidirectional"))
      (node (ref "D14") (pin "P2") (pinfunction "CI_P2") (pintype "bidirectional"))
    )
    (net (code "32") (name "Net-(D13-DO)") (class "Default")
      (node (ref "D13") (pin "P6") (pinfunction "DO_P6") (pintype "bidirectional"))
      (node (ref "D14") (pin "P1") (pinfunction "DI_P1") (pintype "bidirectional"))
    )
    (net (code "33") (name "Net-(D14-CO)") (class "Default")
      (node (ref "D14") (pin "P5") (pinfunction "CO_P5") (pintype "bidirectional"))
      (node (ref "D15") (pin "P2") (pinfunction "CI_P2") (pintype "bidirectional"))
    )
    (net (code "34") (name "Net-(D14-DO)") (class "Default")
      (node (ref "D14") (pin "P6") (pinfunction "DO_P6") (pintype "bidirectional"))
      (node (ref "D15") (pin "P1") (pinfunction "DI_P1") (pintype "bidirectional"))
    )
    (net (code "35") (name "Net-(D15-CO)") (class "Default")
      (node (ref "D15") (pin "P5") (pinfunction "CO_P5") (pintype "bidirectional"))
      (node (ref "D16") (pin "P2") (pinfunction "CI_P2") (pintype "bidirectional"))
    )
    (net (code "36") (name "Net-(D15-DO)") (class "Default")
      (node (ref "D15") (pin "P6") (pinfunction "DO_P6") (pintype "bidirectional"))
      (node (ref "D16") (pin "P1") (pinfunction "DI_P1") (pintype "bidirectional"))
    )
    (net (code "37") (name "Net-(D16-CO)") (class "Default")
      (node (ref "D16") (pin "P5") (pinfunction "CO_P5") (pintype "bidirectional"))
      (node (ref "D17") (pin "P2") (pinfunction "CI_P2") (pintype "bidirectional"))
    )
    (net (code "38") (name "Net-(D16-DO)") (class "Default")
      (node (ref "D16") (pin "P6") (pinfunction "DO_P6") (pintype "bidirectional"))
      (node (ref "D17") (pin "P1") (pinfunction "DI_P1") (pintype "bidirectional"))
    )
    (net (code "39") (name "Net-(D17-CO)") (class "Default")
      (node (ref "D17") (pin "P5") (pinfunction "CO_P5") (pintype "bidirectional"))
      (node (ref "D18") (pin "P2") (pinfunction "CI_P2") (pintype "bidirectional"))
    )
    (net (code "40") (name "Net-(D17-DO)") (class "Default")
      (node (ref "D17") (pin "P6") (pinfunction "DO_P6") (pintype "bidirectional"))
      (node (ref "D18") (pin "P1") (pinfunction "DI_P1") (pintype "bidirectional"))
    )
    (net (code "41") (name "Net-(D18-CO)") (class "Default")
      (node (ref "D18") (pin "P5") (pinfunction "CO_P5") (pintype "bidirectional"))
      (node (ref "D19") (pin "P2") (pinfunction "CI_P2") (pintype "bidirectional"))
    )
    (net (code "42") (name "Net-(D18-DO)") (class "Default")
      (node (ref "D18") (pin "P6") (pinfunction "DO_P6") (pintype "bidirectional"))
      (node (ref "D19") (pin "P1") (pinfunction "DI_P1") (pintype "bidirectional"))
    )
    (net (code "43") (name "Net-(D19-CO)") (class "Default")
      (node (ref "D19") (pin "P5") (pinfunction "CO_P5") (pintype "bidirectional"))
      (node (ref "D20") (pin "P2") (pinfunction "CI_P2") (pintype "bidirectional"))
    )
    (net (code "44") (name "Net-(D19-DO)") (class "Default")
      (node (ref "D19") (pin "P6") (pinfunction "DO_P6") (pintype "bidirectional"))
      (node (ref "D20") (pin "P1") (pinfunction "DI_P1") (pintype "bidirectional"))
    )
    (net (code "45") (name "Net-(D20-CO)") (class "Default")
      (node (ref "D20") (pin "P5") (pinfunction "CO_P5") (pintype "bidirectional"))
      (node (ref "D21") (pin "P2") (pinfunction "CI_P2") (pintype "bidirectional"))
    )
    (net (code "46") (name "Net-(D20-DO)") (class "Default")
      (node (ref "D20") (pin "P6") (pinfunction "DO_P6") (pintype "bidirectional"))
      (node (ref "D21") (pin "P1") (pinfunction "DI_P1") (pintype "bidirectional"))
    )
    (net (code "47") (name "Net-(D21-CO)") (class "Default")
      (node (ref "D21") (pin "P5") (pinfunction "CO_P5") (pintype "bidirectional"))
      (node (ref "D22") (pin "P2") (pinfunction "CI_P2") (pintype "bidirectional"))
    )
    (net (code "48") (name "Net-(D21-DO)") (class "Default")
      (node (ref "D21") (pin "P6") (pinfunction "DO_P6") (pintype "bidirectional"))
      (node (ref "D22") (pin "P1") (pinfunction "DI_P1") (pintype "bidirectional"))
    )
    (net (code "49") (name "Net-(D22-CO)") (class "Default")
      (node (ref "D22") (pin "P5") (pinfunction "CO_P5") (pintype "bidirectional"))
      (node (ref "D23") (pin "P2") (pinfunction "CI_P2") (pintype "bidirectional"))
    )
    (net (code "50") (name "Net-(D22-DO)") (class "Default")
      (node (ref "D22") (pin "P6") (pinfunction "DO_P6") (pintype "bidirectional"))
      (node (ref "D23") (pin "P1") (pinfunction "DI_P1") (pintype "bidirectional"))
    )
    (net (code "51") (name "Net-(D23-CO)") (class "Default")
      (node (ref "D23") (pin "P5") (pinfunction "CO_P5") (pintype "bidirectional"))
      (node (ref "D24") (pin "P2") (pinfunction "CI_P2") (pintype "bidirectional"))
    )
    (net (code "52") (name "Net-(D23-DO)") (class "Default")
      (node (ref "D23") (pin "P6") (pinfunction "DO_P6") (pintype "bidirectional"))
      (node (ref "D24") (pin "P1") (pinfunction "DI_P1") (pintype "bidirectional"))
    )
    (net (code "53") (name "Net-(D24-CO)") (class "Default")
      (node (ref "D24") (pin "P5") (pinfunction "CO_P5") (pintype "bidirectional"))
      (node (ref "D25") (pin "P2") (pinfunction "CI_P2") (pintype "bidirectional"))
    )
    (net (code "54") (name "Net-(D24-DO)") (class "Default")
      (node (ref "D24") (pin "P6") (pinfunction "DO_P6") (pintype "bidirectional"))
      (node (ref "D25") (pin "P1") (pinfunction "DI_P1") (pintype "bidirectional"))
    )
    (net (code "55") (name "Net-(D25-CO)") (class "Default")
      (node (ref "D25") (pin "P5") (pinfunction "CO_P5") (pintype "bidirectional"))
      (node (ref "D26") (pin "P2") (pinfunction "CI_P2") (pintype "bidirectional"))
    )
    (net (code "56") (name "Net-(D25-DO)") (class "Default")
      (node (ref "D25") (pin "P6") (pinfunction "DO_P6") (pintype "bidirectional"))
      (node (ref "D26") (pin "P1") (pinfunction "DI_P1") (pintype "bidirectional"))
    )
    (net (code "57") (name "Net-(D26-CO)") (class "Default")
      (node (ref "D26") (pin "P5") (pinfunction "CO_P5") (pintype "bidirectional"))
      (node (ref "D27") (pin "P2") (pinfunction "CI_P2") (pintype "bidirectional"))
    )
    (net (code "58") (name "Net-(D26-DO)") (class "Default")
      (node (ref "D26") (pin "P6") (pinfunction "DO_P6") (pintype "bidirectional"))
      (node (ref "D27") (pin "P1") (pinfunction "DI_P1") (pintype "bidirectional"))
    )
    (net (code "59") (name "Net-(D27-CO)") (class "Default")
      (node (ref "D27") (pin "P5") (pinfunction "CO_P5") (pintype "bidirectional"))
      (node (ref "D28") (pin "P2") (pinfunction "CI_P2") (pintype "bidirectional"))
    )
    (net (code "60") (name "Net-(D27-DO)") (class "Default")
      (node (ref "D27") (pin "P6") (pinfunction "DO_P6") (pintype "bidirectional"))
      (node (ref "D28") (pin "P1") (pinfunction "DI_P1") (pintype "bidirectional"))
    )
    (net (code "61") (name "Net-(D28-CO)") (class "Default")
      (node (ref "D28") (pin "P5") (pinfunction "CO_P5") (pintype "bidirectional"))
      (node (ref "D29") (pin "P2") (pinfunction "CI_P2") (pintype "bidirectional"))
    )
    (net (code "62") (name "Net-(D28-DO)") (class "Default")
      (node (ref "D28") (pin "P6") (pinfunction "DO_P6") (pintype "bidirectional"))
      (node (ref "D29") (pin "P1") (pinfunction "DI_P1") (pintype "bidirectional"))
    )
    (net (code "63") (name "Net-(D29-CO)") (class "Default")
      (node (ref "D29") (pin "P5") (pinfunction "CO_P5") (pintype "bidirectional"))
      (node (ref "D30") (pin "P2") (pinfunction "CI_P2") (pintype "bidirectional"))
    )
    (net (code "64") (name "Net-(D29-DO)") (class "Default")
      (node (ref "D29") (pin "P6") (pinfunction "DO_P6") (pintype "bidirectional"))
      (node (ref "D30") (pin "P1") (pinfunction "DI_P1") (pintype "bidirectional"))
    )
    (net (code "65") (name "Net-(D30-CO)") (class "Default")
      (node (ref "D30") (pin "P5") (pinfunction "CO_P5") (pintype "bidirectional"))
      (node (ref "D31") (pin "P2") (pinfunction "CI_P2") (pintype "bidirectional"))
    )
    (net (code "66") (name "Net-(D30-DO)") (class "Default")
      (node (ref "D30") (pin "P6") (pinfunction "DO_P6") (pintype "bidirectional"))
      (node (ref "D31") (pin "P1") (pinfunction "DI_P1") (pintype "bidirectional"))
    )
    (net (code "67") (name "Net-(D31-CO)") (class "Default")
      (node (ref "D31") (pin "P5") (pinfunction "CO_P5") (pintype "bidirectional"))
      (node (ref "D32") (pin "P2") (pinfunction "CI_P2") (pintype "bidirectional"))
    )
    (net (code "68") (name "Net-(D31-DO)") (class "Default")
      (node (ref "D31") (pin "P6") (pinfunction "DO_P6") (pintype "bidirectional"))
      (node (ref "D32") (pin "P1") (pinfunction "DI_P1") (pintype "bidirectional"))
    )
    (net (code "69") (name "Net-(D32-CO)") (class "Default")
      (node (ref "D32") (pin "P5") (pinfunction "CO_P5") (pintype "bidirectional"))
      (node (ref "D33") (pin "P2") (pinfunction "CI_P2") (pintype "bidirectional"))
    )
    (net (code "70") (name "Net-(D32-DO)") (class "Default")
      (node (ref "D32") (pin "P6") (pinfunction "DO_P6") (pintype "bidirectional"))
      (node (ref "D33") (pin "P1") (pinfunction "DI_P1") (pintype "bidirectional"))
    )
    (net (code "71") (name "Net-(D33-CO)") (class "Default")
      (node (ref "D33") (pin "P5") (pinfunction "CO_P5") (pintype "bidirectional"))
      (node (ref "D34") (pin "P2") (pinfunction "CI_P2") (pintype "bidirectional"))
    )
    (net (code "72") (name "Net-(D33-DO)") (class "Default")
      (node (ref "D33") (pin "P6") (pinfunction "DO_P6") (pintype "bidirectional"))
      (node (ref "D34") (pin "P1") (pinfunction "DI_P1") (pintype "bidirectional"))
    )
    (net (code "73") (name "Net-(D34-CO)") (class "Default")
      (node (ref "D34") (pin "P5") (pinfunction "CO_P5") (pintype "bidirectional"))
      (node (ref "D35") (pin "P2") (pinfunction "CI_P2") (pintype "bidirectional"))
    )
    (net (code "74") (name "Net-(D34-DO)") (class "Default")
      (node (ref "D34") (pin "P6") (pinfunction "DO_P6") (pintype "bidirectional"))
      (node (ref "D35") (pin "P1") (pinfunction "DI_P1") (pintype "bidirectional"))
    )
    (net (code "75") (name "Net-(D35-CO)") (class "Default")
      (node (ref "D35") (pin "P5") (pinfunction "CO_P5") (pintype "bidirectional"))
      (node (ref "D36") (pin "P2") (pinfunction "CI_P2") (pintype "bidirectional"))
    )
    (net (code "76") (name "Net-(D35-DO)") (class "Default")
      (node (ref "D35") (pin "P6") (pinfunction "DO_P6") (pintype "bidirectional"))
      (node (ref "D36") (pin "P1") (pinfunction "DI_P1") (pintype "bidirectional"))
    )
    (net (code "77") (name "Net-(D36-CO)") (class "Default")
      (node (ref "D36") (pin "P5") (pinfunction "CO_P5") (pintype "bidirectional"))
      (node (ref "D37") (pin "P2") (pinfunction "CI_P2") (pintype "bidirectional"))
    )
    (net (code "78") (name "Net-(D36-DO)") (class "Default")
      (node (ref "D36") (pin "P6") (pinfunction "DO_P6") (pintype "bidirectional"))
      (node (ref "D37") (pin "P1") (pinfunction "DI_P1") (pintype "bidirectional"))
    )
    (net (code "79") (name "Net-(D37-CO)") (class "Default")
      (node (ref "D37") (pin "P5") (pinfunction "CO_P5") (pintype "bidirectional"))
      (node (ref "D38") (pin "P2") (pinfunction "CI_P2") (pintype "bidirectional"))
    )
    (net (code "80") (name "Net-(D37-DO)") (class "Default")
      (node (ref "D37") (pin "P6") (pinfunction "DO_P6") (pintype "bidirectional"))
      (node (ref "D38") (pin "P1") (pinfunction "DI_P1") (pintype "bidirectional"))
    )
    (net (code "81") (name "Net-(D38-CO)") (class "Default")
      (node (ref "D38") (pin "P5") (pinfunction "CO_P5") (pintype "bidirectional"))
      (node (ref "D39") (pin "P2") (pinfunction "CI_P2") (pintype "bidirectional"))
    )
    (net (code "82") (name "Net-(D38-DO)") (class "Default")
      (node (ref "D38") (pin "P6") (pinfunction "DO_P6") (pintype "bidirectional"))
      (node (ref "D39") (pin "P1") (pinfunction "DI_P1") (pintype "bidirectional"))
    )
    (net (code "83") (name "Net-(D39-CO)") (class "Default")
      (node (ref "D39") (pin "P5") (pinfunction "CO_P5") (pintype "bidirectional"))
      (node (ref "D40") (pin "P2") (pinfunction "CI_P2") (pintype "bidirectional"))
    )
    (net (code "84") (name "Net-(D39-DO)") (class "Default")
      (node (ref "D39") (pin "P6") (pinfunction "DO_P6") (pintype "bidirectional"))
      (node (ref "D40") (pin "P1") (pinfunction "DI_P1") (pintype "bidirectional"))
    )
    (net (code "85") (name "Net-(D40-CO)") (class "Default")
      (node (ref "D40") (pin "P5") (pinfunction "CO_P5") (pintype "bidirectional"))
      (node (ref "D41") (pin "P2") (pinfunction "CI_P2") (pintype "bidirectional"))
    )
    (net (code "86") (name "Net-(D40-DO)") (class "Default")
      (node (ref "D40") (pin "P6") (pinfunction "DO_P6") (pintype "bidirectional"))
      (node (ref "D41") (pin "P1") (pinfunction "DI_P1") (pintype "bidirectional"))
    )
    (net (code "87") (name "Net-(D41-CO)") (class "Default")
      (node (ref "D41") (pin "P5") (pinfunction "CO_P5") (pintype "bidirectional"))
      (node (ref "D42") (pin "P2") (pinfunction "CI_P2") (pintype "bidirectional"))
    )
    (net (code "88") (name "Net-(D41-DO)") (class "Default")
      (node (ref "D41") (pin "P6") (pinfunction "DO_P6") (pintype "bidirectional"))
      (node (ref "D42") (pin "P1") (pinfunction "DI_P1") (pintype "bidirectional"))
    )
    (net (code "89") (name "Net-(D42-CO)") (class "Default")
      (node (ref "D42") (pin "P5") (pinfunction "CO_P5") (pintype "bidirectional"))
      (node (ref "D43") (pin "P2") (pinfunction "CI_P2") (pintype "bidirectional"))
    )
    (net (code "90") (name "Net-(D42-DO)") (class "Default")
      (node (ref "D42") (pin "P6") (pinfunction "DO_P6") (pintype "bidirectional"))
      (node (ref "D43") (pin "P1") (pinfunction "DI_P1") (pintype "bidirectional"))
    )
    (net (code "91") (name "Net-(D43-CO)") (class "Default")
      (node (ref "D43") (pin "P5") (pinfunction "CO_P5") (pintype "bidirectional"))
      (node (ref "D44") (pin "P2") (pinfunction "CI_P2") (pintype "bidirectional"))
    )
    (net (code "92") (name "Net-(D43-DO)") (class "Default")
      (node (ref "D43") (pin "P6") (pinfunction "DO_P6") (pintype "bidirectional"))
      (node (ref "D44") (pin "P1") (pinfunction "DI_P1") (pintype "bidirectional"))
    )
    (net (code "93") (name "Net-(D44-CO)") (class "Default")
      (node (ref "D44") (pin "P5") (pinfunction "CO_P5") (pintype "bidirectional"))
      (node (ref "D45") (pin "P2") (pinfunction "CI_P2") (pintype "bidirectional"))
    )
    (net (code "94") (name "Net-(D44-DO)") (class "Default")
      (node (ref "D44") (pin "P6") (pinfunction "DO_P6") (pintype "bidirectional"))
      (node (ref "D45") (pin "P1") (pinfunction "DI_P1") (pintype "bidirectional"))
    )
    (net (code "95") (name "Net-(D45-CO)") (class "Default")
      (node (ref "D45") (pin "P5") (pinfunction "CO_P5") (pintype "bidirectional"))
      (node (ref "D46") (pin "P2") (pinfunction "CI_P2") (pintype "bidirectional"))
    )
    (net (code "96") (name "Net-(D45-DO)") (class "Default")
      (node (ref "D45") (pin "P6") (pinfunction "DO_P6") (pintype "bidirectional"))
      (node (ref "D46") (pin "P1") (pinfunction "DI_P1") (pintype "bidirectional"))
    )
    (net (code "97") (name "Net-(D46-CO)") (class "Default")
      (node (ref "D46") (pin "P5") (pinfunction "CO_P5") (pintype "bidirectional"))
      (node (ref "D47") (pin "P2") (pinfunction "CI_P2") (pintype "bidirectional"))
    )
    (net (code "98") (name "Net-(D46-DO)") (class "Default")
      (node (ref "D46") (pin "P6") (pinfunction "DO_P6") (pintype "bidirectional"))
      (node (ref "D47") (pin "P1") (pinfunction "DI_P1") (pintype "bidirectional"))
    )
    (net (code "99") (name "Net-(D47-CO)") (class "Default")
      (node (ref "D47") (pin "P5") (pinfunction "CO_P5") (pintype "bidirectional"))
      (node (ref "D48") (pin "P2") (pinfunction "CI_P2") (pintype "bidirectional"))
    )
    (net (code "100") (name "Net-(D47-DO)") (class "Default")
      (node (ref "D47") (pin "P6") (pinfunction "DO_P6") (pintype "bidirectional"))
      (node (ref "D48") (pin "P1") (pinfunction "DI_P1") (pintype "bidirectional"))
    )
    (net (code "101") (name "Net-(D48-CO)") (class "Default")
      (node (ref "D48") (pin "P5") (pinfunction "CO_P5") (pintype "bidirectional"))
      (node (ref "D49") (pin "P2") (pinfunction "CI_P2") (pintype "bidirectional"))
    )
    (net (code "102") (name "Net-(D48-DO)") (class "Default")
      (node (ref "D48") (pin "P6") (pinfunction "DO_P6") (pintype "bidirectional"))
      (node (ref "D49") (pin "P1") (pinfunction "DI_P1") (pintype "bidirectional"))
    )
    (net (code "103") (name "Net-(D49-CO)") (class "Default")
      (node (ref "D49") (pin "P5") (pinfunction "CO_P5") (pintype "bidirectional"))
      (node (ref "D50") (pin "P2") (pinfunction "CI_P2") (pintype "bidirectional"))
    )
    (net (code "104") (name "Net-(D49-DO)") (class "Default")
      (node (ref "D49") (pin "P6") (pinfunction "DO_P6") (pintype "bidirectional"))
      (node (ref "D50") (pin "P1") (pinfunction "DI_P1") (pintype "bidirectional"))
    )
    (net (code "105") (name "Net-(D50-CO)") (class "Default")
      (node (ref "D50") (pin "P5") (pinfunction "CO_P5") (pintype "bidirectional"))
      (node (ref "D51") (pin "P2") (pinfunction "CI_P2") (pintype "bidirectional"))
    )
    (net (code "106") (name "Net-(D50-DO)") (class "Default")
      (node (ref "D50") (pin "P6") (pinfunction "DO_P6") (pintype "bidirectional"))
      (node (ref "D51") (pin "P1") (pinfunction "DI_P1") (pintype "bidirectional"))
    )
    (net (code "107") (name "Net-(D51-CO)") (class "Default")
      (node (ref "D51") (pin "P5") (pinfunction "CO_P5") (pintype "bidirectional"))
      (node (ref "D52") (pin "P2") (pinfunction "CI_P2") (pintype "bidirectional"))
    )
    (net (code "108") (name "Net-(D51-DO)") (class "Default")
      (node (ref "D51") (pin "P6") (pinfunction "DO_P6") (pintype "bidirectional"))
      (node (ref "D52") (pin "P1") (pinfunction "DI_P1") (pintype "bidirectional"))
    )
    (net (code "109") (name "Net-(D52-CO)") (class "Default")
      (node (ref "D52") (pin "P5") (pinfunction "CO_P5") (pintype "bidirectional"))
      (node (ref "D53") (pin "P2") (pinfunction "CI_P2") (pintype "bidirectional"))
    )
    (net (code "110") (name "Net-(D52-DO)") (class "Default")
      (node (ref "D52") (pin "P6") (pinfunction "DO_P6") (pintype "bidirectional"))
      (node (ref "D53") (pin "P1") (pinfunction "DI_P1") (pintype "bidirectional"))
    )
    (net (code "111") (name "Net-(D53-CO)") (class "Default")
      (node (ref "D53") (pin "P5") (pinfunction "CO_P5") (pintype "bidirectional"))
      (node (ref "D54") (pin "P2") (pinfunction "CI_P2") (pintype "bidirectional"))
    )
    (net (code "112") (name "Net-(D53-DO)") (class "Default")
      (node (ref "D53") (pin "P6") (pinfunction "DO_P6") (pintype "bidirectional"))
      (node (ref "D54") (pin "P1") (pinfunction "DI_P1") (pintype "bidirectional"))
    )
    (net (code "113") (name "Net-(J3-2)") (class "Default")
      (node (ref "F1") (pin "1") (pinfunction "1_1") (pintype "bidirectional"))
      (node (ref "J3") (pin "VCC") (pinfunction "2_VCC") (pintype "passive"))
    )
  )
)
